# schematic.net
KiCad netlist of a schematic drawn in EasyEDA
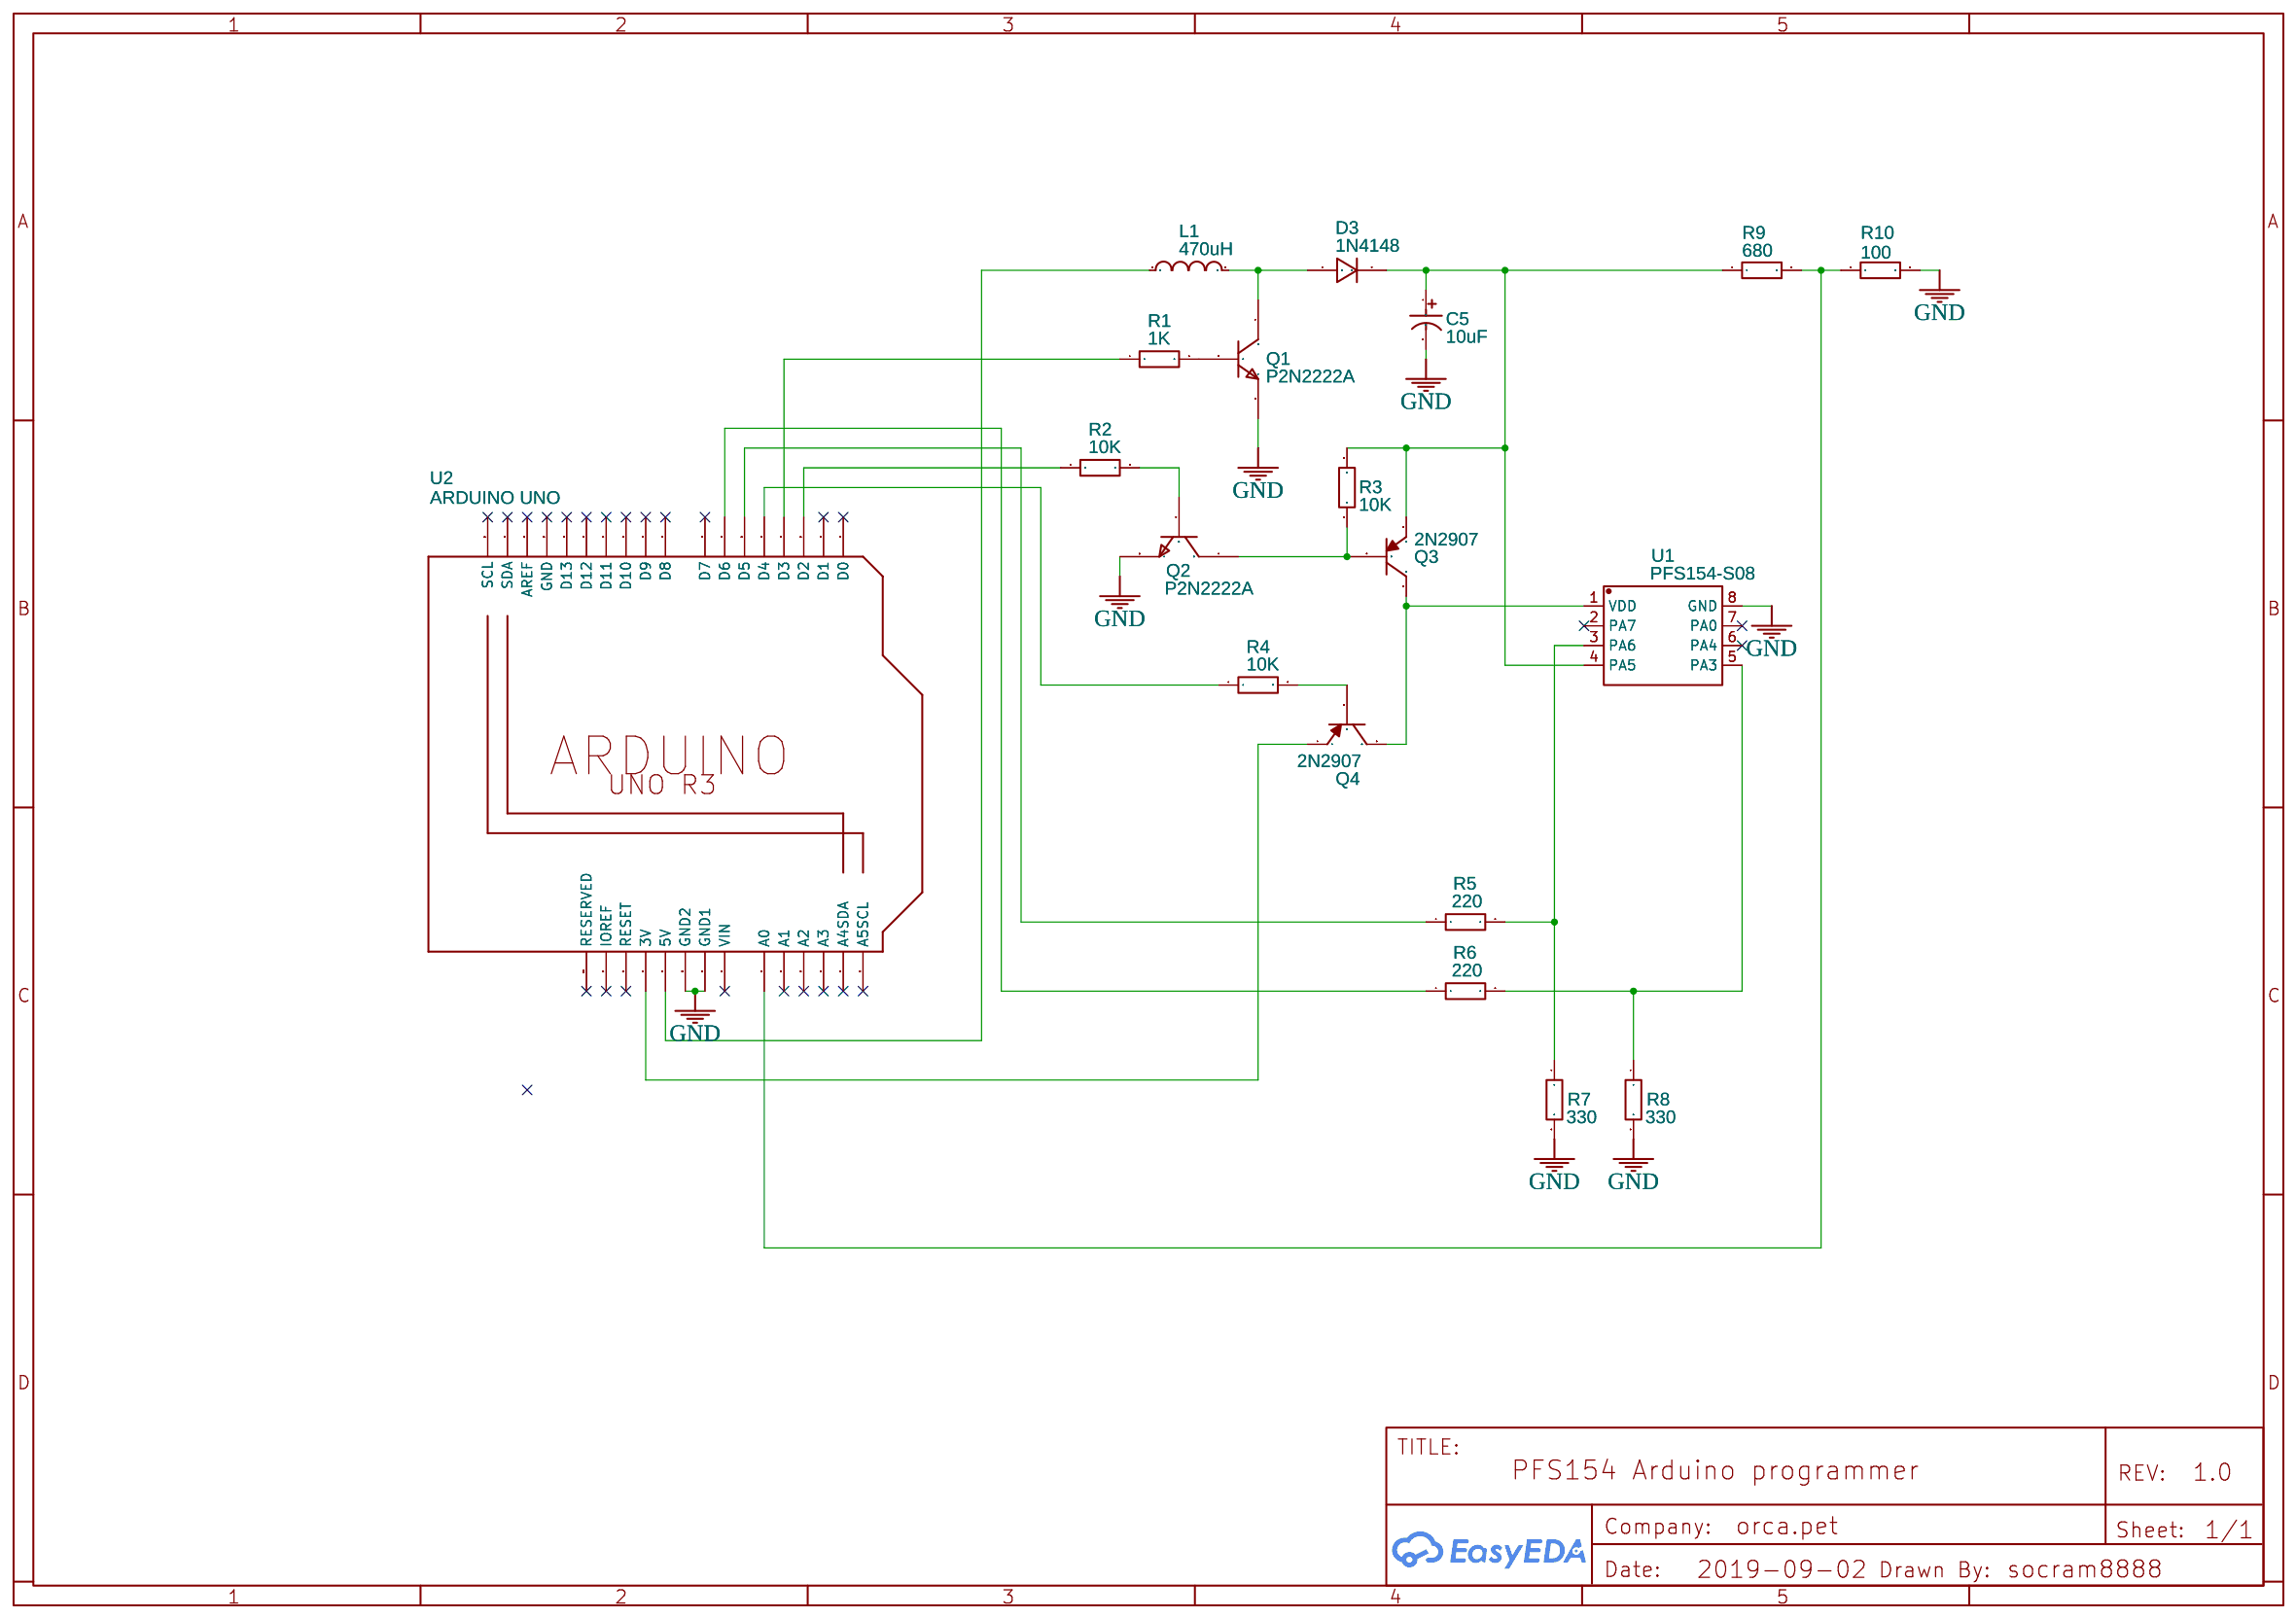
[diagram p0: schematic sheet]

(export (version "E")
  (design (tool "Eeschema 10.0.6"))
  (components
    (comp (ref "C5")
      (value "10uF")
      (fields
        (field (name "BOM_Manufacturer Part") "10uF 25V 4*7")
        (field (name "BOM_Supplier Part") "C43351")
      )
      (libsource (lib "") (part "10uF 25V 4*7"))
    )
    (comp (ref "D3")
      (value "1N4148")
      (fields (field (name "BOM_Supplier Part") "C163750"))
      (libsource (lib "") (part "Unknown_675_130"))
    )
    (comp (ref "L1")
      (value "470uH")
      (fields
        (field (name "BOM_Manufacturer Part") "VLU0810-471K")
        (field (name "BOM_Supplier Part") "C72619")
      )
      (libsource (lib "") (part "VLU0810-471K"))
    )
    (comp (ref "Q1") (value "P2N2222A") (libsource (lib "") (part "Unknown_615_175")))
    (comp (ref "Q2") (value "P2N2222A") (libsource (lib "") (part "Unknown_590_260")))
    (comp (ref "Q3")
      (value "2N2907")
      (fields (field (name "BOM_Supplier Part") "C118537"))
      (libsource (lib "") (part "Unknown_690_275"))
    )
    (comp (ref "Q4")
      (value "2N2907")
      (fields (field (name "BOM_Supplier Part") "C118537"))
      (libsource (lib "") (part "Unknown_675_355"))
    )
    (comp (ref "R1")
      (value "1K")
      (fields (field (name "BOM_Supplier Part") "C337047"))
      (libsource (lib "") (part "MF1/8W ±2% 1Ω8 OTB5_1"))
    )
    (comp (ref "R2")
      (value "10K")
      (fields (field (name "BOM_Supplier Part") "C337047"))
      (libsource (lib "") (part "MF1/8W ±2% 1Ω8 OTB5_1"))
    )
    (comp (ref "R3")
      (value "10K")
      (fields (field (name "BOM_Supplier Part") "C337047"))
      (libsource (lib "") (part "MF1/8W ±2% 1Ω8 OTB5"))
    )
    (comp (ref "R4")
      (value "10K")
      (fields (field (name "BOM_Supplier Part") "C337047"))
      (libsource (lib "") (part "MF1/8W ±2% 1Ω8 OTB5_1"))
    )
    (comp (ref "R5")
      (value "220")
      (fields (field (name "BOM_Supplier Part") "C337127"))
      (libsource (lib "") (part "MF1/8W ±1% 220Ω OTB5"))
    )
    (comp (ref "R6")
      (value "220")
      (fields (field (name "BOM_Supplier Part") "C337127"))
      (libsource (lib "") (part "MF1/8W ±1% 220Ω OTB5"))
    )
    (comp (ref "R7")
      (value "330")
      (fields
        (field (name "BOM_Manufacturer Part") "MFR0W8F3300A50")
        (field (name "BOM_Supplier Part") "C81959")
      )
      (libsource (lib "") (part "MFR0W8F3300A50"))
    )
    (comp (ref "R8")
      (value "330")
      (fields
        (field (name "BOM_Manufacturer Part") "MFR0W8F3300A50")
        (field (name "BOM_Supplier Part") "C81959")
      )
      (libsource (lib "") (part "MFR0W8F3300A50"))
    )
    (comp (ref "R9")
      (value "680")
      (fields
        (field (name "BOM_Manufacturer Part") "MFR-25FTE52-680K")
        (field (name "BOM_Supplier Part") "C173038")
      )
      (libsource (lib "") (part "MFR-25FTE52-680K"))
    )
    (comp (ref "R10")
      (value "100")
      (fields
        (field (name "BOM_Manufacturer Part") "MFR-25FTE52-68R")
        (field (name "BOM_Supplier Part") "C173041")
      )
      (libsource (lib "") (part "MFR-25FTE52-68R"))
    )
    (comp (ref "U1")
      (value "PFS154-S08")
      (fields (field (name "BOM_Supplier Part") "C317611"))
      (libsource (lib "") (part "Unknown_835_315"))
    )
    (comp (ref "U2") (value "ARDUINO UNO") (libsource (lib "") (part "Unknown_335_375")))
  )
  (nets
    (net (code "1") (name "GND") (class "Default")
      (node (ref "C5") (pin "2") (pinfunction "2_2") (pintype "input"))
      (node (ref "Q1") (pin "3") (pinfunction "E_3") (pintype "unspecified"))
      (node (ref "Q2") (pin "3") (pinfunction "E_3") (pintype "unspecified"))
      (node (ref "R10") (pin "2") (pinfunction "2_2") (pintype "unspecified"))
      (node (ref "R7") (pin "2") (pinfunction "2_2") (pintype "unspecified"))
      (node (ref "R8") (pin "2") (pinfunction "2_2") (pintype "unspecified"))
      (node (ref "U1") (pin "8") (pinfunction "GND_8") (pintype "unspecified"))
      (node (ref "U2") (pin "GND1") (pinfunction "GND1_GND1") (pintype "passive"))
      (node (ref "U2") (pin "GND2") (pinfunction "GND2_GND2") (pintype "passive"))
    )
    (net (code "2") (name "Net-(L1-Pad1)") (class "Default")
      (node (ref "L1") (pin "1") (pinfunction "1_1") (pintype "unspecified"))
      (node (ref "U2") (pin "5V") (pinfunction "5V_5V") (pintype "passive"))
    )
    (net (code "3") (name "Net-(Q1-B)") (class "Default")
      (node (ref "Q1") (pin "2") (pinfunction "B_2") (pintype "unspecified"))
      (node (ref "R1") (pin "2") (pinfunction "2_2") (pintype "unspecified"))
    )
    (net (code "4") (name "Net-(Q1-C)") (class "Default")
      (node (ref "D3") (pin "1") (pinfunction "1_1") (pintype "unspecified"))
      (node (ref "L1") (pin "2") (pinfunction "2_2") (pintype "unspecified"))
      (node (ref "Q1") (pin "1") (pinfunction "C_1") (pintype "unspecified"))
    )
    (net (code "5") (name "Net-(Q2-B)") (class "Default")
      (node (ref "Q2") (pin "2") (pinfunction "B_2") (pintype "unspecified"))
      (node (ref "R2") (pin "2") (pinfunction "2_2") (pintype "unspecified"))
    )
    (net (code "6") (name "Net-(Q2-C)") (class "Default")
      (node (ref "Q2") (pin "1") (pinfunction "C_1") (pintype "unspecified"))
      (node (ref "Q3") (pin "2") (pinfunction "B_2") (pintype "unspecified"))
      (node (ref "R3") (pin "1") (pinfunction "1_1") (pintype "unspecified"))
    )
    (net (code "7") (name "Net-(Q3-C)") (class "Default")
      (node (ref "Q3") (pin "3") (pinfunction "C_3") (pintype "unspecified"))
      (node (ref "Q4") (pin "3") (pinfunction "C_3") (pintype "unspecified"))
      (node (ref "U1") (pin "1") (pinfunction "VDD_1") (pintype "unspecified"))
    )
    (net (code "8") (name "Net-(Q3-E)") (class "Default")
      (node (ref "C5") (pin "1") (pinfunction "1_1") (pintype "input"))
      (node (ref "D3") (pin "2") (pinfunction "2_2") (pintype "unspecified"))
      (node (ref "Q3") (pin "1") (pinfunction "E_1") (pintype "unspecified"))
      (node (ref "R3") (pin "2") (pinfunction "2_2") (pintype "unspecified"))
      (node (ref "R9") (pin "1") (pinfunction "1_1") (pintype "unspecified"))
      (node (ref "U1") (pin "4") (pinfunction "PA5_4") (pintype "unspecified"))
    )
    (net (code "9") (name "Net-(Q4-B)") (class "Default")
      (node (ref "Q4") (pin "2") (pinfunction "B_2") (pintype "unspecified"))
      (node (ref "R4") (pin "2") (pinfunction "2_2") (pintype "unspecified"))
    )
    (net (code "10") (name "Net-(Q4-E)") (class "Default")
      (node (ref "Q4") (pin "1") (pinfunction "E_1") (pintype "unspecified"))
      (node (ref "U2") (pin "3V") (pinfunction "3V_3V") (pintype "passive"))
    )
    (net (code "11") (name "Net-(R1-Pad1)") (class "Default")
      (node (ref "R1") (pin "1") (pinfunction "1_1") (pintype "unspecified"))
      (node (ref "U2") (pin "D3") (pinfunction "D3_D3") (pintype "unspecified"))
    )
    (net (code "12") (name "Net-(R2-Pad1)") (class "Default")
      (node (ref "R2") (pin "1") (pinfunction "1_1") (pintype "unspecified"))
      (node (ref "U2") (pin "D2") (pinfunction "D2_D2") (pintype "unspecified"))
    )
    (net (code "13") (name "Net-(R4-Pad1)") (class "Default")
      (node (ref "R4") (pin "1") (pinfunction "1_1") (pintype "unspecified"))
      (node (ref "U2") (pin "D4") (pinfunction "D4_D4") (pintype "unspecified"))
    )
    (net (code "14") (name "Net-(R5-Pad1)") (class "Default")
      (node (ref "R5") (pin "1") (pinfunction "1_1") (pintype "unspecified"))
      (node (ref "U2") (pin "D5") (pinfunction "D5_D5") (pintype "unspecified"))
    )
    (net (code "15") (name "Net-(R6-Pad1)") (class "Default")
      (node (ref "R6") (pin "1") (pinfunction "1_1") (pintype "unspecified"))
      (node (ref "U2") (pin "D6") (pinfunction "D6_D6") (pintype "unspecified"))
    )
    (net (code "16") (name "Net-(R10-Pad1)") (class "Default")
      (node (ref "R10") (pin "1") (pinfunction "1_1") (pintype "unspecified"))
      (node (ref "R9") (pin "2") (pinfunction "2_2") (pintype "unspecified"))
      (node (ref "U2") (pin "A0") (pinfunction "A0_A0") (pintype "unspecified"))
    )
    (net (code "17") (name "Net-(U1-PA3)") (class "Default")
      (node (ref "R6") (pin "2") (pinfunction "2_2") (pintype "unspecified"))
      (node (ref "R8") (pin "1") (pinfunction "1_1") (pintype "unspecified"))
      (node (ref "U1") (pin "5") (pinfunction "PA3_5") (pintype "unspecified"))
    )
    (net (code "18") (name "Net-(U1-PA6)") (class "Default")
      (node (ref "R5") (pin "2") (pinfunction "2_2") (pintype "unspecified"))
      (node (ref "R7") (pin "1") (pinfunction "1_1") (pintype "unspecified"))
      (node (ref "U1") (pin "3") (pinfunction "PA6_3") (pintype "unspecified"))
    )
    (net (code "19") (name "unconnected-(U1-PA0-Pad7)") (class "Default")
      (node (ref "U1") (pin "7") (pinfunction "PA0_7") (pintype "unspecified+no_connect"))
    )
    (net (code "20") (name "unconnected-(U1-PA4-Pad6)") (class "Default")
      (node (ref "U1") (pin "6") (pinfunction "PA4_6") (pintype "unspecified+no_connect"))
    )
    (net (code "21") (name "unconnected-(U1-PA7-Pad2)") (class "Default")
      (node (ref "U1") (pin "2") (pinfunction "PA7_2") (pintype "unspecified+no_connect"))
    )
    (net (code "22") (name "unconnected-(U2-A4SDA-PadA4)") (class "Default")
      (node (ref "U2") (pin "A4") (pinfunction "A4SDA_A4") (pintype "unspecified+no_connect"))
    )
    (net (code "23") (name "unconnected-(U2-A5SCL-PadA5)") (class "Default")
      (node (ref "U2") (pin "A5") (pinfunction "A5SCL_A5") (pintype "unspecified+no_connect"))
    )
    (net (code "24") (name "unconnected-(U2-PadA1)") (class "Default")
      (node (ref "U2") (pin "A1") (pinfunction "A1_A1") (pintype "unspecified+no_connect"))
    )
    (net (code "25") (name "unconnected-(U2-PadA2)") (class "Default")
      (node (ref "U2") (pin "A2") (pinfunction "A2_A2") (pintype "unspecified+no_connect"))
    )
    (net (code "26") (name "unconnected-(U2-PadA3)") (class "Default")
      (node (ref "U2") (pin "A3") (pinfunction "A3_A3") (pintype "unspecified+no_connect"))
    )
    (net (code "27") (name "unconnected-(U2-PadAREF)") (class "Default")
      (node (ref "U2") (pin "AREF") (pinfunction "AREF_AREF") (pintype "unspecified+no_connect"))
    )
    (net (code "28") (name "unconnected-(U2-PadD0)") (class "Default")
      (node (ref "U2") (pin "D0") (pinfunction "D0_D0") (pintype "unspecified+no_connect"))
    )
    (net (code "29") (name "unconnected-(U2-PadD1)") (class "Default")
      (node (ref "U2") (pin "D1") (pinfunction "D1_D1") (pintype "unspecified+no_connect"))
    )
    (net (code "30") (name "unconnected-(U2-PadD7)") (class "Default")
      (node (ref "U2") (pin "D7") (pinfunction "D7_D7") (pintype "unspecified+no_connect"))
    )
    (net (code "31") (name "unconnected-(U2-PadD8)") (class "Default")
      (node (ref "U2") (pin "D8") (pinfunction "D8_D8") (pintype "unspecified+no_connect"))
    )
    (net (code "32") (name "unconnected-(U2-PadD9)") (class "Default")
      (node (ref "U2") (pin "D9") (pinfunction "D9_D9") (pintype "unspecified+no_connect"))
    )
    (net (code "33") (name "unconnected-(U2-PadD10)") (class "Default")
      (node (ref "U2") (pin "D10") (pinfunction "D10_D10") (pintype "unspecified+no_connect"))
    )
    (net (code "34") (name "unconnected-(U2-PadD11)") (class "Default")
      (node (ref "U2") (pin "D11") (pinfunction "D11_D11") (pintype "unspecified+no_connect"))
    )
    (net (code "35") (name "unconnected-(U2-PadD12)") (class "Default")
      (node (ref "U2") (pin "D12") (pinfunction "D12_D12") (pintype "unspecified+no_connect"))
    )
    (net (code "36") (name "unconnected-(U2-PadD13)") (class "Default")
      (node (ref "U2") (pin "D13") (pinfunction "D13_D13") (pintype "unspecified+no_connect"))
    )
    (net (code "37") (name "unconnected-(U2-PadGND)") (class "Default")
      (node (ref "U2") (pin "GND") (pinfunction "GND_GND") (pintype "passive+no_connect"))
    )
    (net (code "38") (name "unconnected-(U2-PadIOREF)") (class "Default")
      (node (ref "U2") (pin "IOREF") (pinfunction "IOREF_IOREF") (pintype "output+no_connect"))
    )
    (net (code "39") (name "unconnected-(U2-PadRESERVED)") (class "Default")
      (node (ref "U2") (pin "RESERVED") (pinfunction "RESERVED_RESERVED") (pintype "unspecified+no_connect"))
    )
    (net (code "40") (name "unconnected-(U2-PadRESET)") (class "Default")
      (node (ref "U2") (pin "RESET") (pinfunction "RESET_RESET") (pintype "unspecified+no_connect"))
    )
    (net (code "41") (name "unconnected-(U2-PadSCL)") (class "Default")
      (node (ref "U2") (pin "SCL") (pinfunction "SCL_SCL") (pintype "unspecified+no_connect"))
    )
    (net (code "42") (name "unconnected-(U2-PadSDA)") (class "Default")
      (node (ref "U2") (pin "SDA") (pinfunction "SDA_SDA") (pintype "unspecified+no_connect"))
    )
    (net (code "43") (name "unconnected-(U2-PadVIN)") (class "Default")
      (node (ref "U2") (pin "VIN") (pinfunction "VIN_VIN") (pintype "passive+no_connect"))
    )
  )
)
